# SCH_Key_chain_Finder1_2023-02-19.net
KiCad netlist of a schematic drawn in EasyEDA
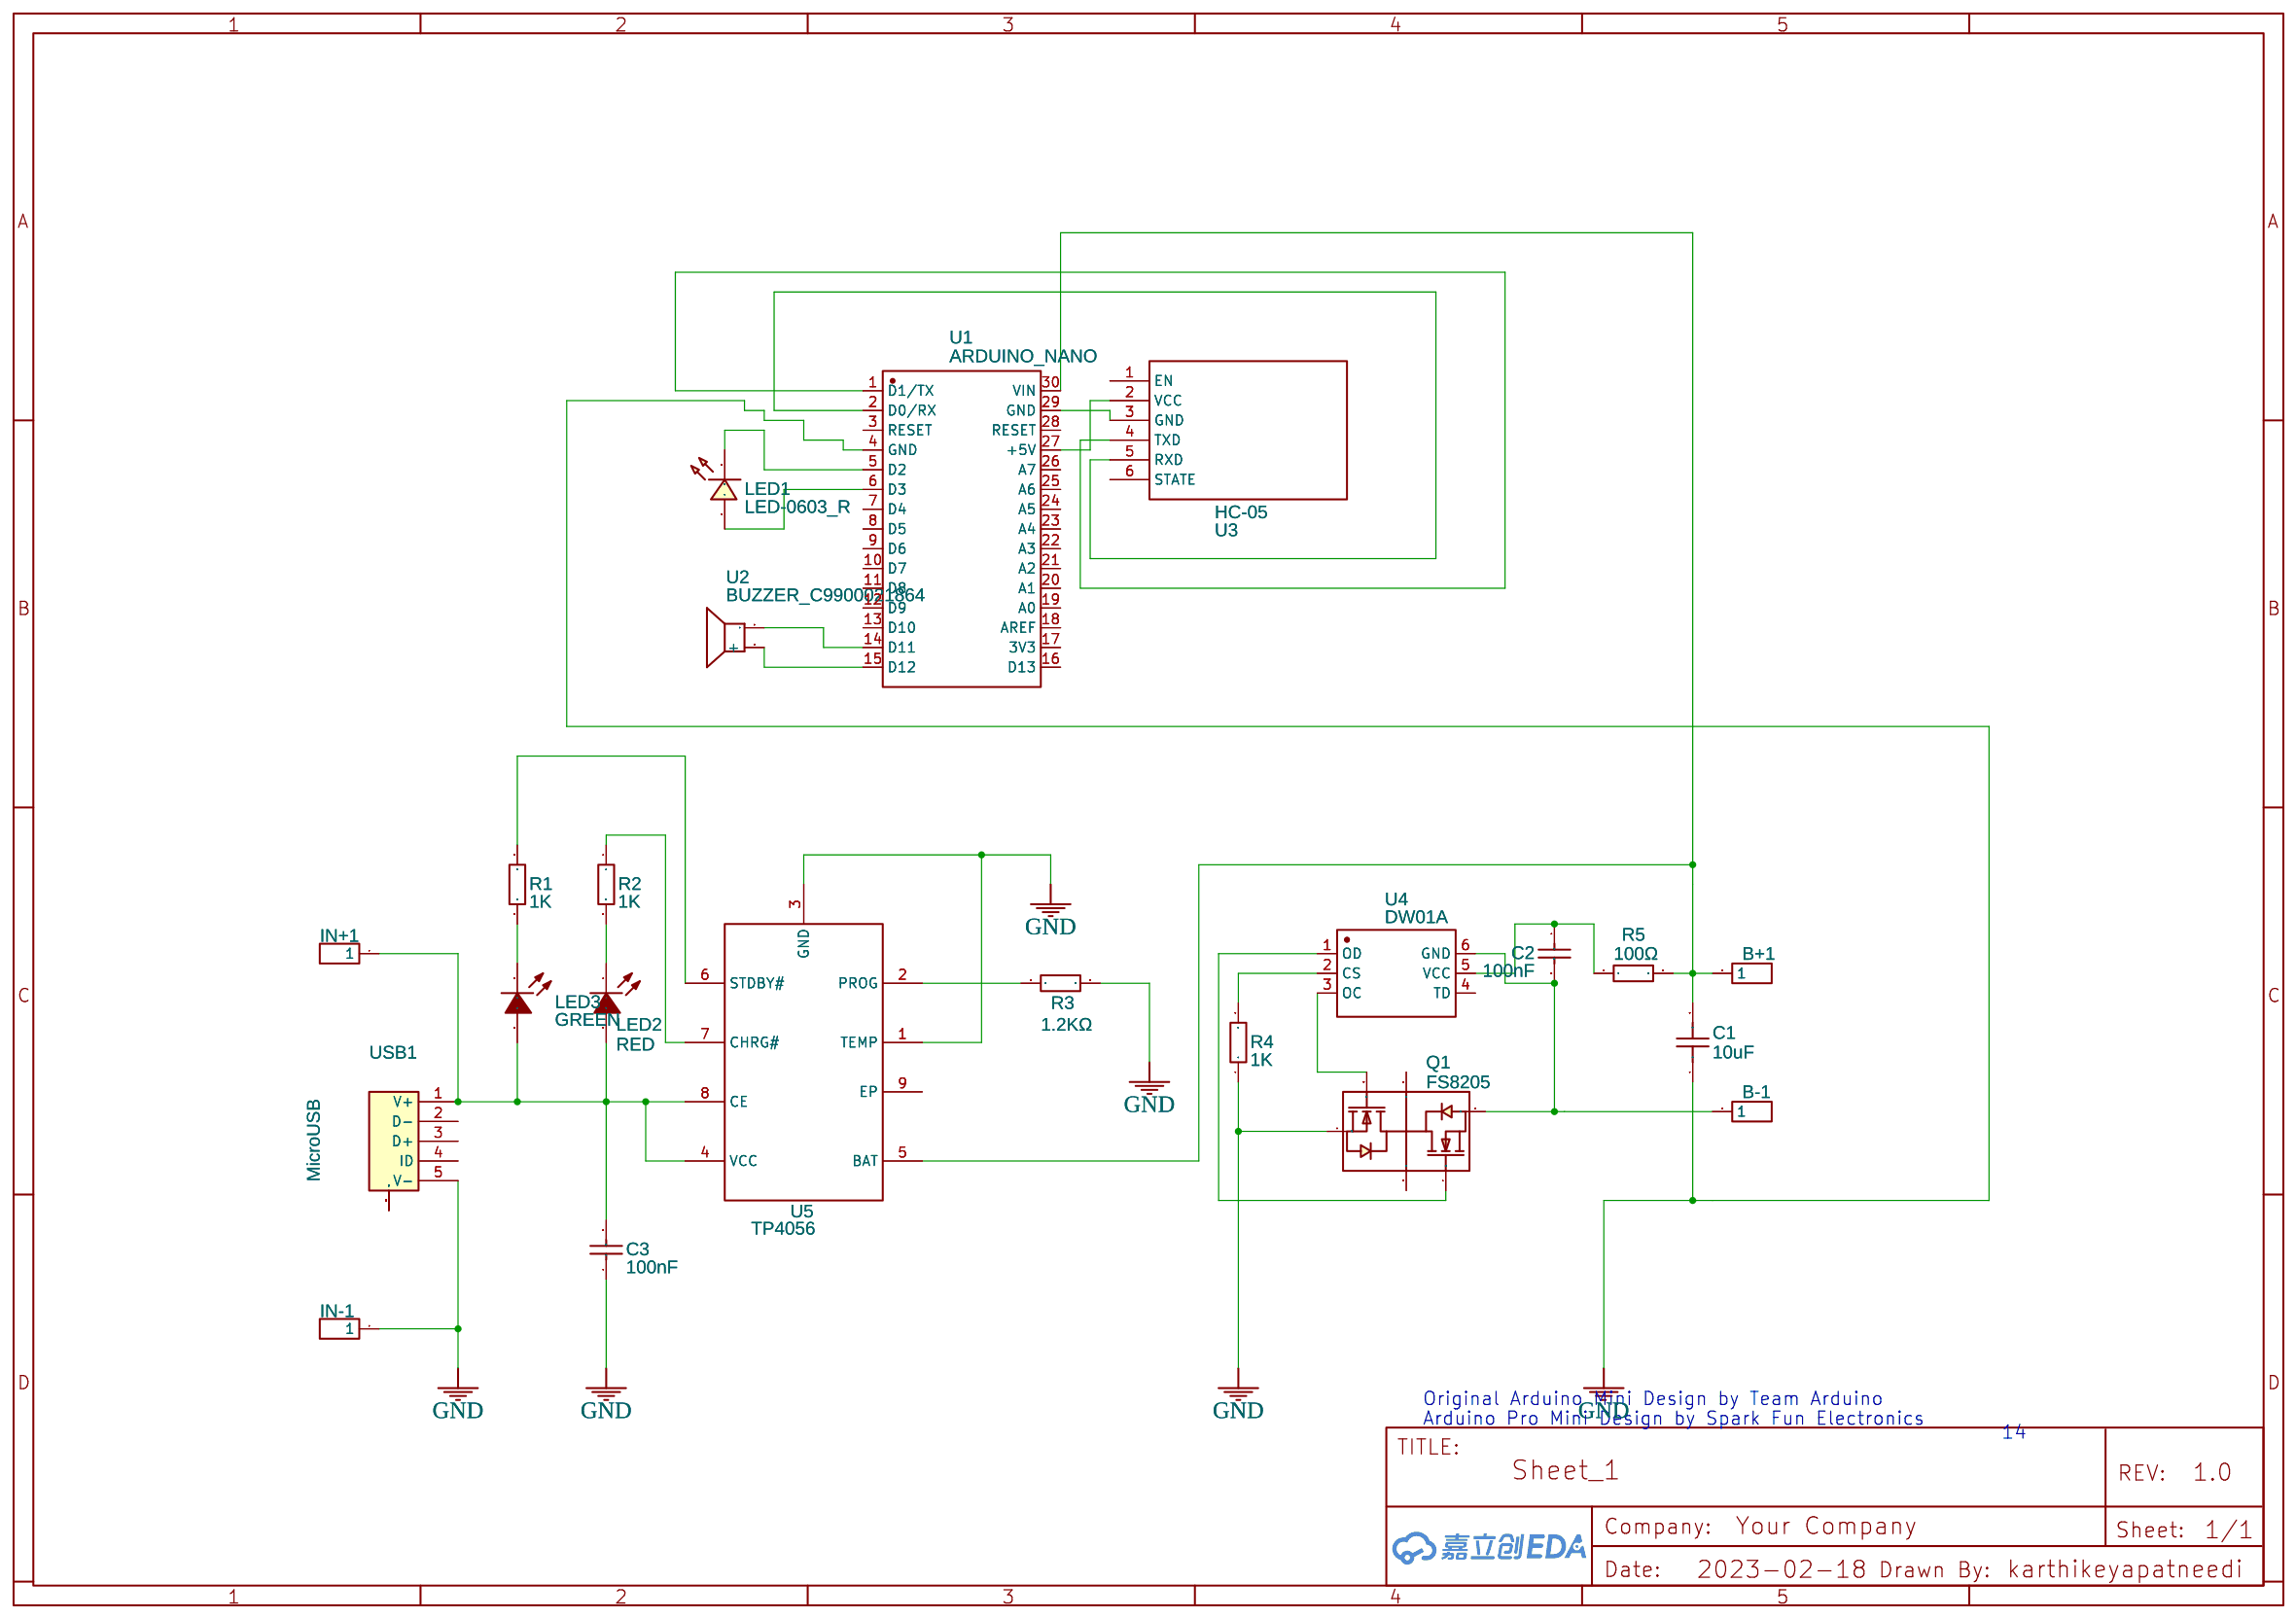
[diagram p0: schematic sheet]

(export (version "E")
  (design (tool "Eeschema 10.0.6"))
  (components
    (comp (ref "B+1")
      (value "Header-Male-2.54_1x1")
      (fields (field (name "BOM_Supplier Part") "C81276"))
      (libsource (lib "") (part "Unknown_875_-320"))
    )
    (comp (ref "B-1")
      (value "Header-Male-2.54_1x1")
      (fields (field (name "BOM_Supplier Part") "C81276"))
      (libsource (lib "") (part "Unknown_875_-250"))
    )
    (comp (ref "C1")
      (value "10uF")
      (fields
        (field (name "BOM_Manufacturer Part") "CL10A106MP8NNNC")
        (field (name "BOM_Supplier Part") "C85713")
      )
      (libsource (lib "") (part "CL10A106MP8NNNC"))
    )
    (comp (ref "C2")
      (value "100nF")
      (fields
        (field (name "BOM_Manufacturer Part") "0603B104K250CT")
        (field (name "BOM_Supplier Part") "C83054")
      )
      (libsource (lib "") (part "0603B104K250"))
    )
    (comp (ref "C3")
      (value "100nF")
      (fields
        (field (name "BOM_Manufacturer Part") "0603B104K250CT")
        (field (name "BOM_Supplier Part") "C83054")
      )
      (libsource (lib "") (part "0603B104K250_1"))
    )
    (comp (ref "IN+1")
      (value "Header-Male-2.54_1x1")
      (fields (field (name "BOM_Manufacturer Part") "2.54-1*1P针") (field (name "BOM_Supplier Part") "C81276"))
      (libsource (lib "") (part "Header-Male-2.54_1x1_1"))
    )
    (comp (ref "IN-1")
      (value "Header-Male-2.54_1x1")
      (fields (field (name "BOM_Manufacturer Part") "2.54-1*1P针") (field (name "BOM_Supplier Part") "C81276"))
      (libsource (lib "") (part "Header-Male-2.54_1x1"))
    )
    (comp (ref "LED1")
      (value "LED-0603_R")
      (fields
        (field (name "BOM_Manufacturer Part") "19-217/R6C-AL1M2VY/3T")
        (field (name "BOM_Supplier Part") "C72044")
      )
      (libsource (lib "") (part "LED-0603_R"))
    )
    (comp (ref "LED2")
      (value "RED")
      (fields
        (field (name "BOM_Manufacturer Part") "LTST-C191KRKT")
        (field (name "BOM_Supplier Part") "C125099")
      )
      (libsource (lib "") (part "LTST-C191KRKT"))
    )
    (comp (ref "LED3")
      (value "GREEN")
      (fields
        (field (name "BOM_Manufacturer Part") "LTST-C193TGKT-5A")
        (field (name "BOM_Supplier Part") "C12065")
      )
      (libsource (lib "") (part "LTST-C193TGKT-5A"))
    )
    (comp (ref "Q1")
      (value "FS8205")
      (fields (field (name "BOM_Supplier Part") "C32254"))
      (libsource (lib "") (part "FS8205"))
    )
    (comp (ref "R1")
      (value "1K")
      (fields
        (field (name "BOM_Manufacturer Part") "ERJ3GEYJ102V")
        (field (name "BOM_Supplier Part") "C180848")
      )
      (libsource (lib "") (part "ERJ3GEYJ102V"))
    )
    (comp (ref "R2")
      (value "1K")
      (fields
        (field (name "BOM_Manufacturer Part") "ERJ3GEYJ102V")
        (field (name "BOM_Supplier Part") "C180848")
      )
      (libsource (lib "") (part "ERJ3GEYJ102V_1"))
    )
    (comp (ref "R3")
      (value "1.2KΩ")
      (fields
        (field (name "BOM_Manufacturer Part") "RC0603JR-071K2L")
        (field (name "BOM_Supplier Part") "C114679")
      )
      (libsource (lib "") (part "RC0603JR-071K2L"))
    )
    (comp (ref "R4")
      (value "1K")
      (fields
        (field (name "BOM_Manufacturer Part") "ERJ3GEYJ102V")
        (field (name "BOM_Supplier Part") "C180848")
      )
      (libsource (lib "") (part "ERJ3GEYJ102V"))
    )
    (comp (ref "R5")
      (value "100Ω")
      (fields
        (field (name "BOM_Manufacturer Part") "0603WAJ0101T5E")
        (field (name "BOM_Supplier Part") "C25201")
      )
      (libsource (lib "") (part "0603WAJ0101T5E"))
    )
    (comp (ref "U1")
      (value "ARDUINO_NANO")
      (fields (field (name "BOM_Supplier Part") "C9900017879"))
      (libsource (lib "") (part "ARDUINO_NANO"))
    )
    (comp (ref "U2")
      (value "BUZZER_C9900021864")
      (fields
        (field (name "BOM_Manufacturer Part") "BUZZER")
        (field (name "BOM_Supplier Part") "C9900021864")
      )
      (libsource (lib "") (part "BUZZER_C9900021864"))
    )
    (comp (ref "U3") (value "HC-05") (libsource (lib "") (part "Unknown_555_-620")))
    (comp (ref "U4")
      (value "DW01A")
      (fields (field (name "BOM_Manufacturer Part") "DW01A-G") (field (name "BOM_Supplier Part") "C61503"))
      (libsource (lib "") (part "DW01A-G"))
    )
    (comp (ref "U5")
      (value "TP4056")
      (fields
        (field (name "BOM_Manufacturer Part") "TP4056-42-ESOP8")
        (field (name "BOM_Supplier Part") "C16581")
      )
      (libsource (lib "") (part "TP4056"))
    )
    (comp (ref "USB1")
      (value "MicroUSB")
      (fields
        (field (name "BOM_Manufacturer Part") "920-E52A2021S10100")
        (field (name "BOM_Supplier Part") "C10418")
      )
      (libsource (lib "") (part "micro USBFemale"))
    )
  )
  (nets
    (net (code "1") (name "GND") (class "Default")
      (node (ref "C1") (pin "1") (pinfunction "1_1") (pintype "unspecified"))
      (node (ref "C3") (pin "1") (pinfunction "1_1") (pintype "input"))
      (node (ref "IN-1") (pin "1") (pinfunction "1_1") (pintype "input"))
      (node (ref "Q1") (pin "1") (pinfunction "S1_1") (pintype "unspecified"))
      (node (ref "R3") (pin "2") (pinfunction "2_2") (pintype "input"))
      (node (ref "R4") (pin "1") (pinfunction "1_1") (pintype "unspecified"))
      (node (ref "U1") (pin "4") (pinfunction "GND_4") (pintype "unspecified"))
      (node (ref "U5") (pin "1") (pinfunction "TEMP_1") (pintype "unspecified"))
      (node (ref "U5") (pin "3") (pinfunction "GND_3") (pintype "unspecified"))
      (node (ref "USB1") (pin "5") (pinfunction "V-_5") (pintype "unspecified"))
    )
    (net (code "2") (name "Net-(LED2-+)") (class "Default")
      (node (ref "C3") (pin "2") (pinfunction "2_2") (pintype "input"))
      (node (ref "IN+1") (pin "1") (pinfunction "1_1") (pintype "input"))
      (node (ref "LED2") (pin "2") (pinfunction "+_2") (pintype "unspecified"))
      (node (ref "LED3") (pin "2") (pinfunction "A_2") (pintype "unspecified"))
      (node (ref "U5") (pin "4") (pinfunction "VCC_4") (pintype "unspecified"))
      (node (ref "U5") (pin "8") (pinfunction "CE_8") (pintype "unspecified"))
      (node (ref "USB1") (pin "1") (pinfunction "V+_1") (pintype "unspecified"))
    )
    (net (code "3") (name "Net-(LED2--)") (class "Default")
      (node (ref "LED2") (pin "1") (pinfunction "-_1") (pintype "unspecified"))
      (node (ref "R2") (pin "2") (pinfunction "2_2") (pintype "unspecified"))
    )
    (net (code "4") (name "Net-(LED3-K)") (class "Default")
      (node (ref "LED3") (pin "1") (pinfunction "K_1") (pintype "unspecified"))
      (node (ref "R1") (pin "1") (pinfunction "1_1") (pintype "unspecified"))
    )
    (net (code "5") (name "Net-(Q1-G1)") (class "Default")
      (node (ref "Q1") (pin "6") (pinfunction "G1_6") (pintype "unspecified"))
      (node (ref "U4") (pin "3") (pinfunction "OC_3") (pintype "unspecified"))
    )
    (net (code "6") (name "Net-(Q1-G2)") (class "Default")
      (node (ref "Q1") (pin "4") (pinfunction "G2_4") (pintype "unspecified"))
      (node (ref "U4") (pin "1") (pinfunction "OD_1") (pintype "unspecified"))
    )
    (net (code "7") (name "Net-(Q1-S2)") (class "Default")
      (node (ref "B-1") (pin "1") (pinfunction "1_1") (pintype "input"))
      (node (ref "C2") (pin "2") (pinfunction "2_2") (pintype "input"))
      (node (ref "Q1") (pin "3") (pinfunction "S2_3") (pintype "unspecified"))
      (node (ref "U4") (pin "6") (pinfunction "GND_6") (pintype "unspecified"))
    )
    (net (code "8") (name "Net-(U1-+5V)") (class "Default")
      (node (ref "U1") (pin "27") (pinfunction "+5V_27") (pintype "unspecified"))
      (node (ref "U3") (pin "2") (pinfunction "VCC_2") (pintype "passive"))
    )
    (net (code "9") (name "Net-(U1-D0{slash}RX)") (class "Default")
      (node (ref "U1") (pin "2") (pinfunction "D0/RX_2") (pintype "unspecified"))
      (node (ref "U3") (pin "5") (pinfunction "RXD_5") (pintype "unspecified"))
    )
    (net (code "10") (name "Net-(U1-D1{slash}TX)") (class "Default")
      (node (ref "U1") (pin "1") (pinfunction "D1/TX_1") (pintype "unspecified"))
      (node (ref "U3") (pin "4") (pinfunction "TXD_4") (pintype "unspecified"))
    )
    (net (code "11") (name "Net-(U1-D2)") (class "Default")
      (node (ref "LED1") (pin "2") (pinfunction "2_2") (pintype "unspecified"))
      (node (ref "U1") (pin "5") (pinfunction "D2_5") (pintype "unspecified"))
    )
    (net (code "12") (name "Net-(U1-D3)") (class "Default")
      (node (ref "LED1") (pin "1") (pinfunction "1_1") (pintype "unspecified"))
      (node (ref "U1") (pin "6") (pinfunction "D3_6") (pintype "unspecified"))
    )
    (net (code "13") (name "Net-(U1-D11)") (class "Default")
      (node (ref "U1") (pin "14") (pinfunction "D11_14") (pintype "unspecified"))
      (node (ref "U2") (pin "1") (pinfunction "1_1") (pintype "unspecified"))
    )
    (net (code "14") (name "Net-(U1-D12)") (class "Default")
      (node (ref "U1") (pin "15") (pinfunction "D12_15") (pintype "unspecified"))
      (node (ref "U2") (pin "2") (pinfunction "+_2") (pintype "unspecified"))
    )
    (net (code "15") (name "Net-(U1-VIN)") (class "Default")
      (node (ref "B+1") (pin "1") (pinfunction "1_1") (pintype "input"))
      (node (ref "C1") (pin "2") (pinfunction "2_2") (pintype "unspecified"))
      (node (ref "R5") (pin "2") (pinfunction "2_2") (pintype "input"))
      (node (ref "U1") (pin "30") (pinfunction "VIN_30") (pintype "unspecified"))
      (node (ref "U5") (pin "5") (pinfunction "BAT_5") (pintype "unspecified"))
    )
    (net (code "16") (name "Net-(U3-GND)") (class "Default")
      (node (ref "U1") (pin "29") (pinfunction "GND_29") (pintype "unspecified"))
      (node (ref "U3") (pin "3") (pinfunction "GND_3") (pintype "unspecified"))
    )
    (net (code "17") (name "Net-(U4-CS)") (class "Default")
      (node (ref "R4") (pin "2") (pinfunction "2_2") (pintype "unspecified"))
      (node (ref "U4") (pin "2") (pinfunction "CS_2") (pintype "unspecified"))
    )
    (net (code "18") (name "Net-(U4-VCC)") (class "Default")
      (node (ref "C2") (pin "1") (pinfunction "1_1") (pintype "input"))
      (node (ref "R5") (pin "1") (pinfunction "1_1") (pintype "input"))
      (node (ref "U4") (pin "5") (pinfunction "VCC_5") (pintype "unspecified"))
    )
    (net (code "19") (name "Net-(U5-CHRG#)") (class "Default")
      (node (ref "R2") (pin "1") (pinfunction "1_1") (pintype "unspecified"))
      (node (ref "U5") (pin "7") (pinfunction "CHRG#_7") (pintype "unspecified"))
    )
    (net (code "20") (name "Net-(U5-PROG)") (class "Default")
      (node (ref "R3") (pin "1") (pinfunction "1_1") (pintype "input"))
      (node (ref "U5") (pin "2") (pinfunction "PROG_2") (pintype "unspecified"))
    )
    (net (code "21") (name "Net-(U5-STDBY#)") (class "Default")
      (node (ref "R1") (pin "2") (pinfunction "2_2") (pintype "unspecified"))
      (node (ref "U5") (pin "6") (pinfunction "STDBY#_6") (pintype "unspecified"))
    )
    (net (code "22") (name "Net-(USB1-1)") (class "Default")
      (node (ref "USB1") (pin "SH0") (pinfunction "MTN_SH0") (pintype "input"))
      (node (ref "USB1") (pin "SH1") (pinfunction "1_SH1") (pintype "unspecified"))
      (node (ref "USB1") (pin "SH2") (pinfunction "2_SH2") (pintype "unspecified"))
      (node (ref "USB1") (pin "SH3") (pinfunction "3_SH3") (pintype "unspecified"))
    )
    (net (code "23") (name "unconnected-(Q1-D12-Pad2)") (class "Default")
      (node (ref "Q1") (pin "2") (pinfunction "D12_2") (pintype "unspecified"))
    )
    (net (code "24") (name "unconnected-(Q1-D12-Pad5)") (class "Default")
      (node (ref "Q1") (pin "5") (pinfunction "D12_5") (pintype "unspecified"))
    )
    (net (code "25") (name "unconnected-(U1-3V3-Pad17)") (class "Default")
      (node (ref "U1") (pin "17") (pinfunction "3V3_17") (pintype "unspecified"))
    )
    (net (code "26") (name "unconnected-(U1-A0-Pad19)") (class "Default")
      (node (ref "U1") (pin "19") (pinfunction "A0_19") (pintype "unspecified"))
    )
    (net (code "27") (name "unconnected-(U1-A1-Pad20)") (class "Default")
      (node (ref "U1") (pin "20") (pinfunction "A1_20") (pintype "unspecified"))
    )
    (net (code "28") (name "unconnected-(U1-A2-Pad21)") (class "Default")
      (node (ref "U1") (pin "21") (pinfunction "A2_21") (pintype "unspecified"))
    )
    (net (code "29") (name "unconnected-(U1-A3-Pad22)") (class "Default")
      (node (ref "U1") (pin "22") (pinfunction "A3_22") (pintype "unspecified"))
    )
    (net (code "30") (name "unconnected-(U1-A4-Pad23)") (class "Default")
      (node (ref "U1") (pin "23") (pinfunction "A4_23") (pintype "unspecified"))
    )
    (net (code "31") (name "unconnected-(U1-A5-Pad24)") (class "Default")
      (node (ref "U1") (pin "24") (pinfunction "A5_24") (pintype "unspecified"))
    )
    (net (code "32") (name "unconnected-(U1-A6-Pad25)") (class "Default")
      (node (ref "U1") (pin "25") (pinfunction "A6_25") (pintype "unspecified"))
    )
    (net (code "33") (name "unconnected-(U1-A7-Pad26)") (class "Default")
      (node (ref "U1") (pin "26") (pinfunction "A7_26") (pintype "unspecified"))
    )
    (net (code "34") (name "unconnected-(U1-AREF-Pad18)") (class "Default")
      (node (ref "U1") (pin "18") (pinfunction "AREF_18") (pintype "unspecified"))
    )
    (net (code "35") (name "unconnected-(U1-D4-Pad7)") (class "Default")
      (node (ref "U1") (pin "7") (pinfunction "D4_7") (pintype "unspecified"))
    )
    (net (code "36") (name "unconnected-(U1-D5-Pad8)") (class "Default")
      (node (ref "U1") (pin "8") (pinfunction "D5_8") (pintype "unspecified"))
    )
    (net (code "37") (name "unconnected-(U1-D6-Pad9)") (class "Default")
      (node (ref "U1") (pin "9") (pinfunction "D6_9") (pintype "unspecified"))
    )
    (net (code "38") (name "unconnected-(U1-D7-Pad10)") (class "Default")
      (node (ref "U1") (pin "10") (pinfunction "D7_10") (pintype "unspecified"))
    )
    (net (code "39") (name "unconnected-(U1-D8-Pad11)") (class "Default")
      (node (ref "U1") (pin "11") (pinfunction "D8_11") (pintype "unspecified"))
    )
    (net (code "40") (name "unconnected-(U1-D9-Pad12)") (class "Default")
      (node (ref "U1") (pin "12") (pinfunction "D9_12") (pintype "unspecified"))
    )
    (net (code "41") (name "unconnected-(U1-D10-Pad13)") (class "Default")
      (node (ref "U1") (pin "13") (pinfunction "D10_13") (pintype "unspecified"))
    )
    (net (code "42") (name "unconnected-(U1-D13-Pad16)") (class "Default")
      (node (ref "U1") (pin "16") (pinfunction "D13_16") (pintype "unspecified"))
    )
    (net (code "43") (name "unconnected-(U1-RESET-Pad3)") (class "Default")
      (node (ref "U1") (pin "3") (pinfunction "RESET_3") (pintype "unspecified"))
    )
    (net (code "44") (name "unconnected-(U1-RESET-Pad28)") (class "Default")
      (node (ref "U1") (pin "28") (pinfunction "RESET_28") (pintype "unspecified"))
    )
    (net (code "45") (name "unconnected-(U3-EN-Pad1)") (class "Default")
      (node (ref "U3") (pin "1") (pinfunction "EN_1") (pintype "unspecified"))
    )
    (net (code "46") (name "unconnected-(U3-STATE-Pad6)") (class "Default")
      (node (ref "U3") (pin "6") (pinfunction "STATE_6") (pintype "unspecified"))
    )
    (net (code "47") (name "unconnected-(U4-TD-Pad4)") (class "Default")
      (node (ref "U4") (pin "4") (pinfunction "TD_4") (pintype "unspecified"))
    )
    (net (code "48") (name "unconnected-(U5-EP-Pad9)") (class "Default")
      (node (ref "U5") (pin "9") (pinfunction "EP_9") (pintype "unspecified"))
    )
    (net (code "49") (name "unconnected-(USB1-D+-Pad3)") (class "Default")
      (node (ref "USB1") (pin "3") (pinfunction "D+_3") (pintype "unspecified"))
    )
    (net (code "50") (name "unconnected-(USB1-D--Pad2)") (class "Default")
      (node (ref "USB1") (pin "2") (pinfunction "D-_2") (pintype "unspecified"))
    )
    (net (code "51") (name "unconnected-(USB1-ID-Pad4)") (class "Default")
      (node (ref "USB1") (pin "4") (pinfunction "ID_4") (pintype "unspecified"))
    )
  )
)
